# W512X.net
KiCad netlist of a schematic drawn in EAGLE
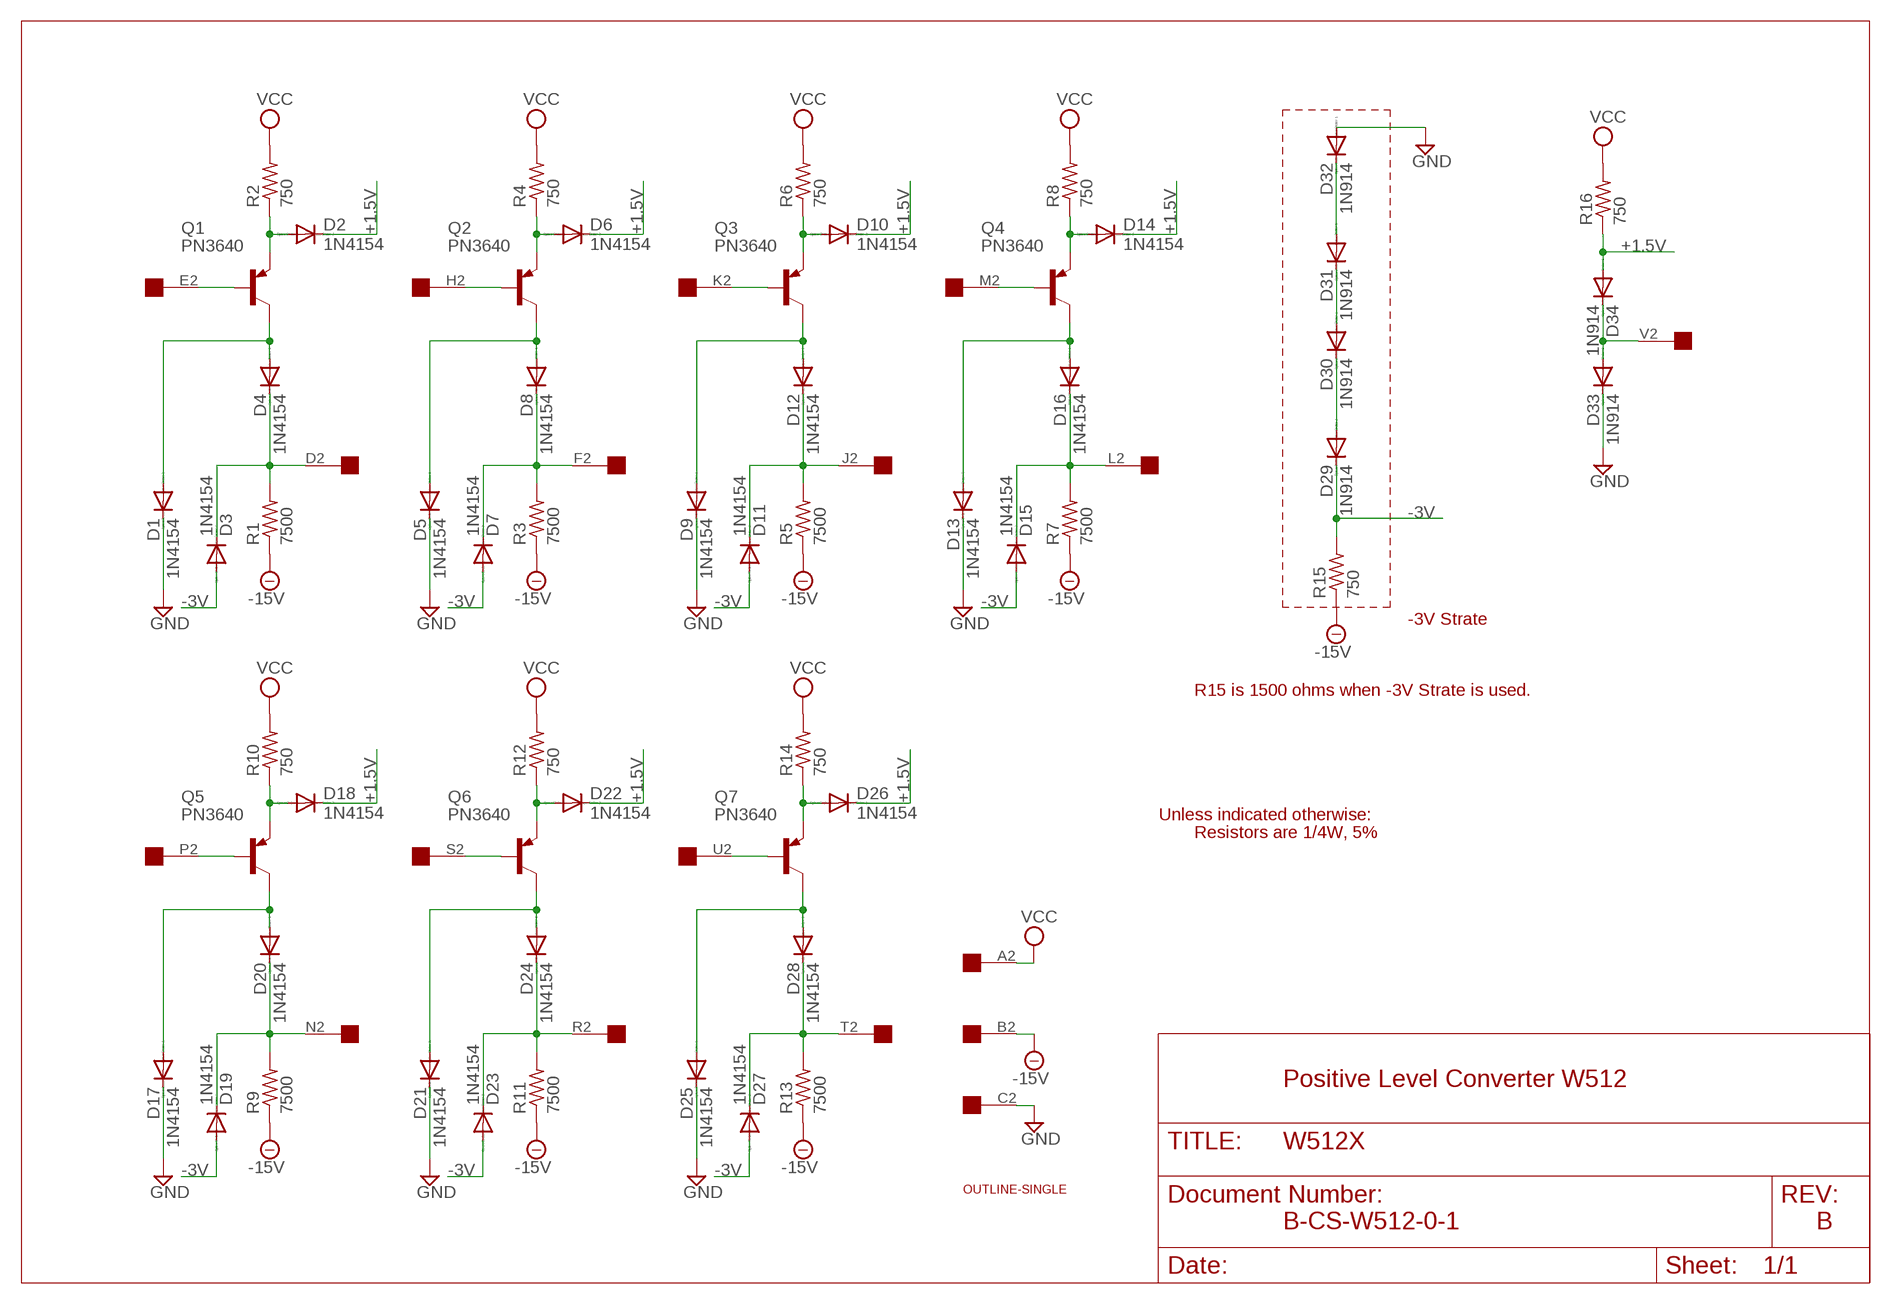
[diagram p0: schematic, sheet 1]

(export (version "E")
  (design (tool "Eeschema 10.0.6"))
  (components
    (comp (ref "D1")
      (value "1N4154")
      (footprint "eagle-import:DO35-10")
      (libsource (lib "eagle-import") (part "1N4148DO35-10"))
    )
    (comp (ref "D2")
      (value "1N4154")
      (footprint "eagle-import:DO35-10")
      (libsource (lib "eagle-import") (part "1N4148DO35-10"))
    )
    (comp (ref "D3")
      (value "1N4154")
      (footprint "eagle-import:DO35-10")
      (libsource (lib "eagle-import") (part "1N4148DO35-10"))
    )
    (comp (ref "D4")
      (value "1N4154")
      (footprint "eagle-import:DO35-10")
      (libsource (lib "eagle-import") (part "1N4148DO35-10"))
    )
    (comp (ref "D5")
      (value "1N4154")
      (footprint "eagle-import:DO35-10")
      (libsource (lib "eagle-import") (part "1N4148DO35-10"))
    )
    (comp (ref "D6")
      (value "1N4154")
      (footprint "eagle-import:DO35-10")
      (libsource (lib "eagle-import") (part "1N4148DO35-10"))
    )
    (comp (ref "D7")
      (value "1N4154")
      (footprint "eagle-import:DO35-10")
      (libsource (lib "eagle-import") (part "1N4148DO35-10"))
    )
    (comp (ref "D8")
      (value "1N4154")
      (footprint "eagle-import:DO35-10")
      (libsource (lib "eagle-import") (part "1N4148DO35-10"))
    )
    (comp (ref "D9")
      (value "1N4154")
      (footprint "eagle-import:DO35-10")
      (libsource (lib "eagle-import") (part "1N4148DO35-10"))
    )
    (comp (ref "D10")
      (value "1N4154")
      (footprint "eagle-import:DO35-10")
      (libsource (lib "eagle-import") (part "1N4148DO35-10"))
    )
    (comp (ref "D11")
      (value "1N4154")
      (footprint "eagle-import:DO35-10")
      (libsource (lib "eagle-import") (part "1N4148DO35-10"))
    )
    (comp (ref "D12")
      (value "1N4154")
      (footprint "eagle-import:DO35-10")
      (libsource (lib "eagle-import") (part "1N4148DO35-10"))
    )
    (comp (ref "D13")
      (value "1N4154")
      (footprint "eagle-import:DO35-10")
      (libsource (lib "eagle-import") (part "1N4148DO35-10"))
    )
    (comp (ref "D14")
      (value "1N4154")
      (footprint "eagle-import:DO35-10")
      (libsource (lib "eagle-import") (part "1N4148DO35-10"))
    )
    (comp (ref "D15")
      (value "1N4154")
      (footprint "eagle-import:DO35-10")
      (libsource (lib "eagle-import") (part "1N4148DO35-10"))
    )
    (comp (ref "D16")
      (value "1N4154")
      (footprint "eagle-import:DO35-10")
      (libsource (lib "eagle-import") (part "1N4148DO35-10"))
    )
    (comp (ref "D17")
      (value "1N4154")
      (footprint "eagle-import:DO35-10")
      (libsource (lib "eagle-import") (part "1N4148DO35-10"))
    )
    (comp (ref "D18")
      (value "1N4154")
      (footprint "eagle-import:DO35-10")
      (libsource (lib "eagle-import") (part "1N4148DO35-10"))
    )
    (comp (ref "D19")
      (value "1N4154")
      (footprint "eagle-import:DO35-10")
      (libsource (lib "eagle-import") (part "1N4148DO35-10"))
    )
    (comp (ref "D20")
      (value "1N4154")
      (footprint "eagle-import:DO35-10")
      (libsource (lib "eagle-import") (part "1N4148DO35-10"))
    )
    (comp (ref "D21")
      (value "1N4154")
      (footprint "eagle-import:DO35-10")
      (libsource (lib "eagle-import") (part "1N4148DO35-10"))
    )
    (comp (ref "D22")
      (value "1N4154")
      (footprint "eagle-import:DO35-10")
      (libsource (lib "eagle-import") (part "1N4148DO35-10"))
    )
    (comp (ref "D23")
      (value "1N4154")
      (footprint "eagle-import:DO35-10")
      (libsource (lib "eagle-import") (part "1N4148DO35-10"))
    )
    (comp (ref "D24")
      (value "1N4154")
      (footprint "eagle-import:DO35-10")
      (libsource (lib "eagle-import") (part "1N4148DO35-10"))
    )
    (comp (ref "D25")
      (value "1N4154")
      (footprint "eagle-import:DO35-10")
      (libsource (lib "eagle-import") (part "1N4148DO35-10"))
    )
    (comp (ref "D26")
      (value "1N4154")
      (footprint "eagle-import:DO35-10")
      (libsource (lib "eagle-import") (part "1N4148DO35-10"))
    )
    (comp (ref "D27")
      (value "1N4154")
      (footprint "eagle-import:DO35-10")
      (libsource (lib "eagle-import") (part "1N4148DO35-10"))
    )
    (comp (ref "D28")
      (value "1N4154")
      (footprint "eagle-import:DO35-10")
      (libsource (lib "eagle-import") (part "1N4148DO35-10"))
    )
    (comp (ref "D29")
      (value "1N914")
      (footprint "eagle-import:DO35-10")
      (libsource (lib "eagle-import") (part "1N4148DO35-10"))
    )
    (comp (ref "D30")
      (value "1N914")
      (footprint "eagle-import:DO35-10")
      (libsource (lib "eagle-import") (part "1N4148DO35-10"))
    )
    (comp (ref "D31")
      (value "1N914")
      (footprint "eagle-import:DO35-10")
      (libsource (lib "eagle-import") (part "1N4148DO35-10"))
    )
    (comp (ref "D32")
      (value "1N914")
      (footprint "eagle-import:DO35-10")
      (libsource (lib "eagle-import") (part "1N4148DO35-10"))
    )
    (comp (ref "D33")
      (value "1N914")
      (footprint "eagle-import:DO35-10")
      (libsource (lib "eagle-import") (part "1N4148DO35-10"))
    )
    (comp (ref "D34")
      (value "1N914")
      (footprint "eagle-import:DO35-10")
      (libsource (lib "eagle-import") (part "1N4148DO35-10"))
    )
    (comp (ref "EDGE")
      (value "EDGE-1")
      (footprint "eagle-import:EDGE-CON1")
      (libsource (lib "eagle-import") (part "EDGE-1"))
    )
    (comp (ref "Q1")
      (value "PN3640")
      (footprint "eagle-import:TO39")
      (libsource (lib "eagle-import") (part "2N2904"))
    )
    (comp (ref "Q2")
      (value "PN3640")
      (footprint "eagle-import:TO39")
      (libsource (lib "eagle-import") (part "2N2904"))
    )
    (comp (ref "Q3")
      (value "PN3640")
      (footprint "eagle-import:TO39")
      (libsource (lib "eagle-import") (part "2N2904"))
    )
    (comp (ref "Q4")
      (value "PN3640")
      (footprint "eagle-import:TO39")
      (libsource (lib "eagle-import") (part "2N2904"))
    )
    (comp (ref "Q5")
      (value "PN3640")
      (footprint "eagle-import:TO39")
      (libsource (lib "eagle-import") (part "2N2904"))
    )
    (comp (ref "Q6")
      (value "PN3640")
      (footprint "eagle-import:TO39")
      (libsource (lib "eagle-import") (part "2N2904"))
    )
    (comp (ref "Q7")
      (value "PN3640")
      (footprint "eagle-import:TO39")
      (libsource (lib "eagle-import") (part "2N2904"))
    )
    (comp (ref "R1")
      (value "7500")
      (footprint "eagle-import:0207_10")
      (libsource (lib "eagle-import") (part "R-US_0207/10"))
    )
    (comp (ref "R2")
      (value "750")
      (footprint "eagle-import:0207_10")
      (libsource (lib "eagle-import") (part "R-US_0207/10"))
    )
    (comp (ref "R3")
      (value "7500")
      (footprint "eagle-import:0207_10")
      (libsource (lib "eagle-import") (part "R-US_0207/10"))
    )
    (comp (ref "R4")
      (value "750")
      (footprint "eagle-import:0207_10")
      (libsource (lib "eagle-import") (part "R-US_0207/10"))
    )
    (comp (ref "R5")
      (value "7500")
      (footprint "eagle-import:0207_10")
      (libsource (lib "eagle-import") (part "R-US_0207/10"))
    )
    (comp (ref "R6")
      (value "750")
      (footprint "eagle-import:0207_10")
      (libsource (lib "eagle-import") (part "R-US_0207/10"))
    )
    (comp (ref "R7")
      (value "7500")
      (footprint "eagle-import:0207_10")
      (libsource (lib "eagle-import") (part "R-US_0207/10"))
    )
    (comp (ref "R8")
      (value "750")
      (footprint "eagle-import:0207_10")
      (libsource (lib "eagle-import") (part "R-US_0207/10"))
    )
    (comp (ref "R9")
      (value "7500")
      (footprint "eagle-import:0207_10")
      (libsource (lib "eagle-import") (part "R-US_0207/10"))
    )
    (comp (ref "R10")
      (value "750")
      (footprint "eagle-import:0207_10")
      (libsource (lib "eagle-import") (part "R-US_0207/10"))
    )
    (comp (ref "R11")
      (value "7500")
      (footprint "eagle-import:0207_10")
      (libsource (lib "eagle-import") (part "R-US_0207/10"))
    )
    (comp (ref "R12")
      (value "750")
      (footprint "eagle-import:0207_10")
      (libsource (lib "eagle-import") (part "R-US_0207/10"))
    )
    (comp (ref "R13")
      (value "7500")
      (footprint "eagle-import:0207_10")
      (libsource (lib "eagle-import") (part "R-US_0207/10"))
    )
    (comp (ref "R14")
      (value "750")
      (footprint "eagle-import:0207_10")
      (libsource (lib "eagle-import") (part "R-US_0207/10"))
    )
    (comp (ref "R15")
      (value "750")
      (footprint "eagle-import:0207_10")
      (libsource (lib "eagle-import") (part "R-US_0207/10"))
    )
    (comp (ref "R16")
      (value "750")
      (footprint "eagle-import:0207_10")
      (libsource (lib "eagle-import") (part "R-US_0207/10"))
    )
    (comp (ref "U$1")
      (value "OUTLINE-SINGLE")
      (footprint "eagle-import:SINGLE")
      (libsource (lib "eagle-import") (part "OUTLINE-SINGLE"))
    )
  )
  (nets
    (net (code "1") (name "-15V") (class "Default")
      (node (ref "EDGE") (pin "B2") (pinfunction "1_B2") (pintype "bidirectional"))
      (node (ref "R1") (pin "1") (pinfunction "1_1") (pintype "passive"))
      (node (ref "R11") (pin "1") (pinfunction "1_1") (pintype "passive"))
      (node (ref "R13") (pin "1") (pinfunction "1_1") (pintype "passive"))
      (node (ref "R15") (pin "1") (pinfunction "1_1") (pintype "passive"))
      (node (ref "R3") (pin "1") (pinfunction "1_1") (pintype "passive"))
      (node (ref "R5") (pin "1") (pinfunction "1_1") (pintype "passive"))
      (node (ref "R7") (pin "1") (pinfunction "1_1") (pintype "passive"))
      (node (ref "R9") (pin "1") (pinfunction "1_1") (pintype "passive"))
    )
    (net (code "2") (name "/+1.5V") (class "Default")
      (node (ref "D10") (pin "C") (pinfunction "C_C") (pintype "passive"))
      (node (ref "D14") (pin "C") (pinfunction "C_C") (pintype "passive"))
      (node (ref "D18") (pin "C") (pinfunction "C_C") (pintype "passive"))
      (node (ref "D2") (pin "C") (pinfunction "C_C") (pintype "passive"))
      (node (ref "D22") (pin "C") (pinfunction "C_C") (pintype "passive"))
      (node (ref "D26") (pin "C") (pinfunction "C_C") (pintype "passive"))
      (node (ref "D34") (pin "A") (pinfunction "A_A") (pintype "passive"))
      (node (ref "D6") (pin "C") (pinfunction "C_C") (pintype "passive"))
      (node (ref "R16") (pin "1") (pinfunction "1_1") (pintype "passive"))
    )
    (net (code "3") (name "/-3V") (class "Default")
      (node (ref "D11") (pin "A") (pinfunction "A_A") (pintype "passive"))
      (node (ref "D15") (pin "A") (pinfunction "A_A") (pintype "passive"))
      (node (ref "D19") (pin "A") (pinfunction "A_A") (pintype "passive"))
      (node (ref "D23") (pin "A") (pinfunction "A_A") (pintype "passive"))
      (node (ref "D27") (pin "A") (pinfunction "A_A") (pintype "passive"))
      (node (ref "D29") (pin "C") (pinfunction "C_C") (pintype "passive"))
      (node (ref "D3") (pin "A") (pinfunction "A_A") (pintype "passive"))
      (node (ref "D7") (pin "A") (pinfunction "A_A") (pintype "passive"))
      (node (ref "R15") (pin "2") (pinfunction "2_2") (pintype "passive"))
    )
    (net (code "4") (name "GND") (class "Default")
      (node (ref "D1") (pin "C") (pinfunction "C_C") (pintype "passive"))
      (node (ref "D13") (pin "C") (pinfunction "C_C") (pintype "passive"))
      (node (ref "D17") (pin "C") (pinfunction "C_C") (pintype "passive"))
      (node (ref "D21") (pin "C") (pinfunction "C_C") (pintype "passive"))
      (node (ref "D25") (pin "C") (pinfunction "C_C") (pintype "passive"))
      (node (ref "D32") (pin "A") (pinfunction "A_A") (pintype "passive"))
      (node (ref "D33") (pin "C") (pinfunction "C_C") (pintype "passive"))
      (node (ref "D5") (pin "C") (pinfunction "C_C") (pintype "passive"))
      (node (ref "D9") (pin "C") (pinfunction "C_C") (pintype "passive"))
      (node (ref "EDGE") (pin "C2") (pinfunction "1_C2") (pintype "bidirectional"))
    )
    (net (code "5") (name "Net-(D29-PadA)") (class "Default")
      (node (ref "D29") (pin "A") (pinfunction "A_A") (pintype "passive"))
      (node (ref "D30") (pin "C") (pinfunction "C_C") (pintype "passive"))
    )
    (net (code "6") (name "Net-(D30-PadA)") (class "Default")
      (node (ref "D30") (pin "A") (pinfunction "A_A") (pintype "passive"))
      (node (ref "D31") (pin "C") (pinfunction "C_C") (pintype "passive"))
    )
    (net (code "7") (name "Net-(D31-PadA)") (class "Default")
      (node (ref "D31") (pin "A") (pinfunction "A_A") (pintype "passive"))
      (node (ref "D32") (pin "C") (pinfunction "C_C") (pintype "passive"))
    )
    (net (code "8") (name "Net-(EDGED-1)") (class "Default")
      (node (ref "D3") (pin "C") (pinfunction "C_C") (pintype "passive"))
      (node (ref "D4") (pin "C") (pinfunction "C_C") (pintype "passive"))
      (node (ref "EDGE") (pin "D2") (pinfunction "1_D2") (pintype "bidirectional"))
      (node (ref "R1") (pin "2") (pinfunction "2_2") (pintype "passive"))
    )
    (net (code "9") (name "Net-(EDGEE-1)") (class "Default")
      (node (ref "EDGE") (pin "E2") (pinfunction "1_E2") (pintype "bidirectional"))
      (node (ref "Q1") (pin "2") (pinfunction "B_2") (pintype "passive"))
    )
    (net (code "10") (name "Net-(EDGEF-1)") (class "Default")
      (node (ref "D7") (pin "C") (pinfunction "C_C") (pintype "passive"))
      (node (ref "D8") (pin "C") (pinfunction "C_C") (pintype "passive"))
      (node (ref "EDGE") (pin "F2") (pinfunction "1_F2") (pintype "bidirectional"))
      (node (ref "R3") (pin "2") (pinfunction "2_2") (pintype "passive"))
    )
    (net (code "11") (name "Net-(EDGEG-1)") (class "Default")
      (node (ref "EDGE") (pin "H2") (pinfunction "1_H2") (pintype "bidirectional"))
      (node (ref "Q2") (pin "2") (pinfunction "B_2") (pintype "passive"))
    )
    (net (code "12") (name "Net-(EDGEH-1)") (class "Default")
      (node (ref "D11") (pin "C") (pinfunction "C_C") (pintype "passive"))
      (node (ref "D12") (pin "C") (pinfunction "C_C") (pintype "passive"))
      (node (ref "EDGE") (pin "J2") (pinfunction "1_J2") (pintype "bidirectional"))
      (node (ref "R5") (pin "2") (pinfunction "2_2") (pintype "passive"))
    )
    (net (code "13") (name "Net-(EDGEI-1)") (class "Default")
      (node (ref "EDGE") (pin "K2") (pinfunction "1_K2") (pintype "bidirectional"))
      (node (ref "Q3") (pin "2") (pinfunction "B_2") (pintype "passive"))
    )
    (net (code "14") (name "Net-(EDGEJ-1)") (class "Default")
      (node (ref "D15") (pin "C") (pinfunction "C_C") (pintype "passive"))
      (node (ref "D16") (pin "C") (pinfunction "C_C") (pintype "passive"))
      (node (ref "EDGE") (pin "L2") (pinfunction "1_L2") (pintype "bidirectional"))
      (node (ref "R7") (pin "2") (pinfunction "2_2") (pintype "passive"))
    )
    (net (code "15") (name "Net-(EDGEK-1)") (class "Default")
      (node (ref "EDGE") (pin "M2") (pinfunction "1_M2") (pintype "bidirectional"))
      (node (ref "Q4") (pin "2") (pinfunction "B_2") (pintype "passive"))
    )
    (net (code "16") (name "Net-(EDGEL-1)") (class "Default")
      (node (ref "D19") (pin "C") (pinfunction "C_C") (pintype "passive"))
      (node (ref "D20") (pin "C") (pinfunction "C_C") (pintype "passive"))
      (node (ref "EDGE") (pin "N2") (pinfunction "1_N2") (pintype "bidirectional"))
      (node (ref "R9") (pin "2") (pinfunction "2_2") (pintype "passive"))
    )
    (net (code "17") (name "Net-(EDGEM-1)") (class "Default")
      (node (ref "EDGE") (pin "P2") (pinfunction "1_P2") (pintype "bidirectional"))
      (node (ref "Q5") (pin "2") (pinfunction "B_2") (pintype "passive"))
    )
    (net (code "18") (name "Net-(EDGEN-1)") (class "Default")
      (node (ref "D23") (pin "C") (pinfunction "C_C") (pintype "passive"))
      (node (ref "D24") (pin "C") (pinfunction "C_C") (pintype "passive"))
      (node (ref "EDGE") (pin "R2") (pinfunction "1_R2") (pintype "bidirectional"))
      (node (ref "R11") (pin "2") (pinfunction "2_2") (pintype "passive"))
    )
    (net (code "19") (name "Net-(EDGEO-1)") (class "Default")
      (node (ref "EDGE") (pin "S2") (pinfunction "1_S2") (pintype "bidirectional"))
      (node (ref "Q6") (pin "2") (pinfunction "B_2") (pintype "passive"))
    )
    (net (code "20") (name "Net-(EDGEP-1)") (class "Default")
      (node (ref "D27") (pin "C") (pinfunction "C_C") (pintype "passive"))
      (node (ref "D28") (pin "C") (pinfunction "C_C") (pintype "passive"))
      (node (ref "EDGE") (pin "T2") (pinfunction "1_T2") (pintype "bidirectional"))
      (node (ref "R13") (pin "2") (pinfunction "2_2") (pintype "passive"))
    )
    (net (code "21") (name "Net-(EDGEQ-1)") (class "Default")
      (node (ref "EDGE") (pin "U2") (pinfunction "1_U2") (pintype "bidirectional"))
      (node (ref "Q7") (pin "2") (pinfunction "B_2") (pintype "passive"))
    )
    (net (code "22") (name "Net-(EDGER-1)") (class "Default")
      (node (ref "D33") (pin "A") (pinfunction "A_A") (pintype "passive"))
      (node (ref "D34") (pin "C") (pinfunction "C_C") (pintype "passive"))
      (node (ref "EDGE") (pin "V2") (pinfunction "1_V2") (pintype "bidirectional"))
    )
    (net (code "23") (name "Net-(Q1-C)") (class "Default")
      (node (ref "D1") (pin "A") (pinfunction "A_A") (pintype "passive"))
      (node (ref "D4") (pin "A") (pinfunction "A_A") (pintype "passive"))
      (node (ref "Q1") (pin "3") (pinfunction "C_3") (pintype "passive"))
    )
    (net (code "24") (name "Net-(Q1-E)") (class "Default")
      (node (ref "D2") (pin "A") (pinfunction "A_A") (pintype "passive"))
      (node (ref "Q1") (pin "1") (pinfunction "E_1") (pintype "passive"))
      (node (ref "R2") (pin "1") (pinfunction "1_1") (pintype "passive"))
    )
    (net (code "25") (name "Net-(Q2-C)") (class "Default")
      (node (ref "D5") (pin "A") (pinfunction "A_A") (pintype "passive"))
      (node (ref "D8") (pin "A") (pinfunction "A_A") (pintype "passive"))
      (node (ref "Q2") (pin "3") (pinfunction "C_3") (pintype "passive"))
    )
    (net (code "26") (name "Net-(Q2-E)") (class "Default")
      (node (ref "D6") (pin "A") (pinfunction "A_A") (pintype "passive"))
      (node (ref "Q2") (pin "1") (pinfunction "E_1") (pintype "passive"))
      (node (ref "R4") (pin "1") (pinfunction "1_1") (pintype "passive"))
    )
    (net (code "27") (name "Net-(Q3-C)") (class "Default")
      (node (ref "D12") (pin "A") (pinfunction "A_A") (pintype "passive"))
      (node (ref "D9") (pin "A") (pinfunction "A_A") (pintype "passive"))
      (node (ref "Q3") (pin "3") (pinfunction "C_3") (pintype "passive"))
    )
    (net (code "28") (name "Net-(Q3-E)") (class "Default")
      (node (ref "D10") (pin "A") (pinfunction "A_A") (pintype "passive"))
      (node (ref "Q3") (pin "1") (pinfunction "E_1") (pintype "passive"))
      (node (ref "R6") (pin "1") (pinfunction "1_1") (pintype "passive"))
    )
    (net (code "29") (name "Net-(Q4-C)") (class "Default")
      (node (ref "D13") (pin "A") (pinfunction "A_A") (pintype "passive"))
      (node (ref "D16") (pin "A") (pinfunction "A_A") (pintype "passive"))
      (node (ref "Q4") (pin "3") (pinfunction "C_3") (pintype "passive"))
    )
    (net (code "30") (name "Net-(Q4-E)") (class "Default")
      (node (ref "D14") (pin "A") (pinfunction "A_A") (pintype "passive"))
      (node (ref "Q4") (pin "1") (pinfunction "E_1") (pintype "passive"))
      (node (ref "R8") (pin "1") (pinfunction "1_1") (pintype "passive"))
    )
    (net (code "31") (name "Net-(Q5-C)") (class "Default")
      (node (ref "D17") (pin "A") (pinfunction "A_A") (pintype "passive"))
      (node (ref "D20") (pin "A") (pinfunction "A_A") (pintype "passive"))
      (node (ref "Q5") (pin "3") (pinfunction "C_3") (pintype "passive"))
    )
    (net (code "32") (name "Net-(Q5-E)") (class "Default")
      (node (ref "D18") (pin "A") (pinfunction "A_A") (pintype "passive"))
      (node (ref "Q5") (pin "1") (pinfunction "E_1") (pintype "passive"))
      (node (ref "R10") (pin "1") (pinfunction "1_1") (pintype "passive"))
    )
    (net (code "33") (name "Net-(Q6-C)") (class "Default")
      (node (ref "D21") (pin "A") (pinfunction "A_A") (pintype "passive"))
      (node (ref "D24") (pin "A") (pinfunction "A_A") (pintype "passive"))
      (node (ref "Q6") (pin "3") (pinfunction "C_3") (pintype "passive"))
    )
    (net (code "34") (name "Net-(Q6-E)") (class "Default")
      (node (ref "D22") (pin "A") (pinfunction "A_A") (pintype "passive"))
      (node (ref "Q6") (pin "1") (pinfunction "E_1") (pintype "passive"))
      (node (ref "R12") (pin "1") (pinfunction "1_1") (pintype "passive"))
    )
    (net (code "35") (name "Net-(Q7-C)") (class "Default")
      (node (ref "D25") (pin "A") (pinfunction "A_A") (pintype "passive"))
      (node (ref "D28") (pin "A") (pinfunction "A_A") (pintype "passive"))
      (node (ref "Q7") (pin "3") (pinfunction "C_3") (pintype "passive"))
    )
    (net (code "36") (name "Net-(Q7-E)") (class "Default")
      (node (ref "D26") (pin "A") (pinfunction "A_A") (pintype "passive"))
      (node (ref "Q7") (pin "1") (pinfunction "E_1") (pintype "passive"))
      (node (ref "R14") (pin "1") (pinfunction "1_1") (pintype "passive"))
    )
    (net (code "37") (name "VCC") (class "Default")
      (node (ref "EDGE") (pin "A2") (pinfunction "1_A2") (pintype "bidirectional"))
      (node (ref "R10") (pin "2") (pinfunction "2_2") (pintype "passive"))
      (node (ref "R12") (pin "2") (pinfunction "2_2") (pintype "passive"))
      (node (ref "R14") (pin "2") (pinfunction "2_2") (pintype "passive"))
      (node (ref "R16") (pin "2") (pinfunction "2_2") (pintype "passive"))
      (node (ref "R2") (pin "2") (pinfunction "2_2") (pintype "passive"))
      (node (ref "R4") (pin "2") (pinfunction "2_2") (pintype "passive"))
      (node (ref "R6") (pin "2") (pinfunction "2_2") (pintype "passive"))
      (node (ref "R8") (pin "2") (pinfunction "2_2") (pintype "passive"))
    )
  )
)
